# CoolderPSU.net
KiCad netlist of a schematic drawn in EAGLE
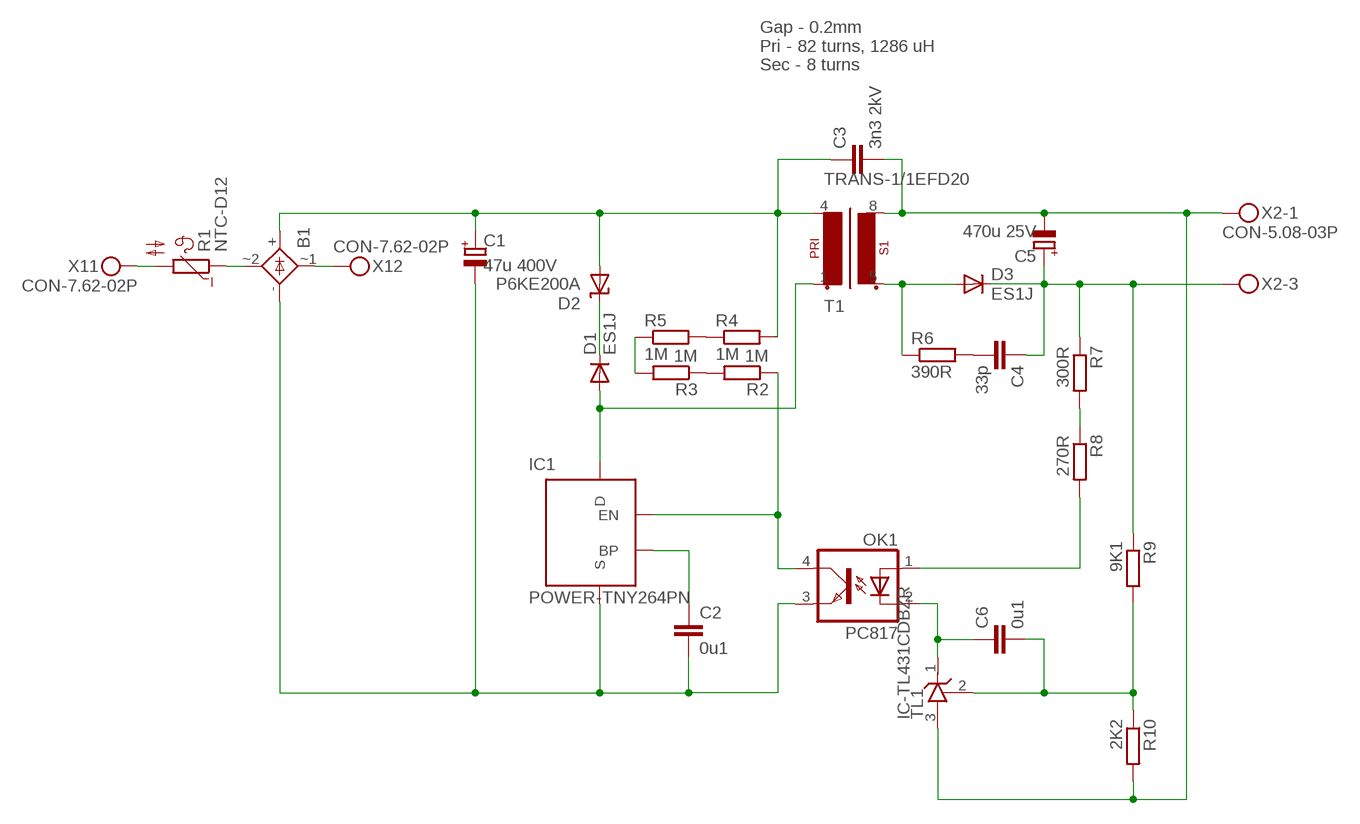
[diagram p0: schematic, sheet 1]

(export (version "E")
  (design (tool "Eeschema 10.0.6"))
  (components
    (comp (ref "B1")
      (value "RECTIFIERSOIC-8")
      (footprint "eagle-import:SOIC-4")
      (libsource (lib "eagle-import") (part "RECTIFIERSOIC-8"))
    )
    (comp (ref "C1")
      (value "47u 400V")
      (footprint "eagle-import:E7,5-16-32-HORIZ")
      (libsource (lib "eagle-import") (part "CAP-POL_E7,5-16"))
    )
    (comp (ref "C2")
      (value "0u1")
      (footprint "eagle-import:C0805")
      (libsource (lib "eagle-import") (part "CAP_0805"))
    )
    (comp (ref "C3")
      (value "3n3 2kV")
      (footprint "eagle-import:C050-024X044")
      (libsource (lib "eagle-import") (part "CAP_C50-024X044"))
    )
    (comp (ref "C4")
      (value "33p")
      (footprint "eagle-import:C0805")
      (libsource (lib "eagle-import") (part "CAP_0805"))
    )
    (comp (ref "C5")
      (value "470u 25V")
      (footprint "eagle-import:E2,5-7")
      (libsource (lib "eagle-import") (part "CAP-POL_E2.5-7"))
    )
    (comp (ref "C6")
      (value "0u1")
      (footprint "eagle-import:C0805")
      (libsource (lib "eagle-import") (part "CAP_0805"))
    )
    (comp (ref "D1")
      (value "ES1J")
      (footprint "eagle-import:DO214AC")
      (libsource (lib "eagle-import") (part "DIODE_ES1J"))
    )
    (comp (ref "D2")
      (value "P6KE200A")
      (footprint "eagle-import:DO15-12")
      (libsource (lib "eagle-import") (part "SUPRESSORDO-204AC"))
    )
    (comp (ref "D3")
      (value "ES1J")
      (footprint "eagle-import:DO214AC")
      (libsource (lib "eagle-import") (part "DIODE_ES1J"))
    )
    (comp (ref "IC1")
      (value "POWER-TNY264PN")
      (footprint "eagle-import:DIP-8B")
      (libsource (lib "eagle-import") (part "POWER-TNY264PN"))
    )
    (comp (ref "OK1")
      (value "PC817")
      (footprint "eagle-import:DIL04")
      (fields (field (name "MPN") "PC817X4J000F"))
      (libsource (lib "eagle-import") (part "OPTOTRANSPC817"))
    )
    (comp (ref "R1")
      (value "NTC-D12")
      (footprint "eagle-import:NTC-D12")
      (libsource (lib "eagle-import") (part "NTC-D12"))
    )
    (comp (ref "R2")
      (value "1M")
      (footprint "eagle-import:R1206")
      (libsource (lib "eagle-import") (part "R_1206"))
    )
    (comp (ref "R3")
      (value "1M")
      (footprint "eagle-import:R1206")
      (libsource (lib "eagle-import") (part "R_1206"))
    )
    (comp (ref "R4")
      (value "1M")
      (footprint "eagle-import:R1206")
      (libsource (lib "eagle-import") (part "R_1206"))
    )
    (comp (ref "R5")
      (value "1M")
      (footprint "eagle-import:R1206")
      (libsource (lib "eagle-import") (part "R_1206"))
    )
    (comp (ref "R6")
      (value "390R")
      (footprint "eagle-import:R1206")
      (libsource (lib "eagle-import") (part "R_1206"))
    )
    (comp (ref "R7")
      (value "300R")
      (footprint "eagle-import:R1206")
      (libsource (lib "eagle-import") (part "R_1206"))
    )
    (comp (ref "R8")
      (value "270R")
      (footprint "eagle-import:R1206")
      (libsource (lib "eagle-import") (part "R_1206"))
    )
    (comp (ref "R9")
      (value "9K1")
      (footprint "eagle-import:R1206")
      (libsource (lib "eagle-import") (part "R_1206"))
    )
    (comp (ref "R10")
      (value "2K2")
      (footprint "eagle-import:R1206")
      (libsource (lib "eagle-import") (part "R_1206"))
    )
    (comp (ref "T1")
      (value "TRANS-1/1EFD20")
      (footprint "eagle-import:EFD20_8PIN")
      (libsource (lib "eagle-import") (part "TRANS-1/1EFD20"))
    )
    (comp (ref "TL1")
      (value "IC-TL431CDBZR")
      (footprint "eagle-import:SOT23")
      (libsource (lib "eagle-import") (part "IC-TL431CDBZR"))
    )
    (comp (ref "X1")
      (value "CON-7.62-02P")
      (footprint "eagle-import:KF25C-7.62-02P-13")
      (libsource (lib "eagle-import") (part "CON-7.62-02P"))
    )
    (comp (ref "X2")
      (value "CON-5.08-03P")
      (footprint "eagle-import:MKDSN1,5_3-5,08")
      (libsource (lib "eagle-import") (part "CON-5.08-03P"))
    )
  )
  (nets
    (net (code "1") (name "Net-(B1-AC1)") (class "Default")
      (node (ref "B1") (pin "~1") (pinfunction "AC1_~1") (pintype "passive"))
      (node (ref "X1") (pin "P$2") (pinfunction "KL_P$2") (pintype "passive"))
    )
    (net (code "2") (name "Net-(B1-AC2)") (class "Default")
      (node (ref "B1") (pin "~2") (pinfunction "AC2_~2") (pintype "passive"))
      (node (ref "R1") (pin "1") (pinfunction "1_1") (pintype "passive"))
    )
    (net (code "3") (name "Net-(C4-Pad2)") (class "Default")
      (node (ref "C4") (pin "2") (pinfunction "2_2") (pintype "passive"))
      (node (ref "R6") (pin "2") (pinfunction "2_2") (pintype "passive"))
    )
    (net (code "4") (name "Net-(D1-PadC)") (class "Default")
      (node (ref "D1") (pin "C") (pinfunction "C_C") (pintype "passive"))
      (node (ref "D2") (pin "C") (pinfunction "C_C") (pintype "passive"))
    )
    (net (code "5") (name "Net-(IC1-BP)") (class "Default")
      (node (ref "C2") (pin "1") (pinfunction "1_1") (pintype "passive"))
      (node (ref "IC1") (pin "1") (pinfunction "BP_1") (pintype "input"))
    )
    (net (code "6") (name "Net-(IC1-D)") (class "Default")
      (node (ref "D1") (pin "A") (pinfunction "A_A") (pintype "passive"))
      (node (ref "IC1") (pin "5") (pinfunction "D_5") (pintype "input"))
      (node (ref "T1") (pin "1") (pinfunction "P1-1_1") (pintype "passive"))
    )
    (net (code "7") (name "Net-(IC1-EN)") (class "Default")
      (node (ref "IC1") (pin "4") (pinfunction "EN_4") (pintype "input"))
      (node (ref "OK1") (pin "4") (pinfunction "COL_4") (pintype "passive"))
      (node (ref "R2") (pin "1") (pinfunction "1_1") (pintype "passive"))
    )
    (net (code "8") (name "Net-(OK1-A)") (class "Default")
      (node (ref "OK1") (pin "1") (pinfunction "A_1") (pintype "passive"))
      (node (ref "R8") (pin "2") (pinfunction "2_2") (pintype "passive"))
    )
    (net (code "9") (name "Net-(OK1-C)") (class "Default")
      (node (ref "C6") (pin "1") (pinfunction "1_1") (pintype "passive"))
      (node (ref "OK1") (pin "2") (pinfunction "C_2") (pintype "passive"))
      (node (ref "TL1") (pin "1") (pinfunction "C_1") (pintype "passive"))
    )
    (net (code "10") (name "Net-(OK1-EMIT)") (class "Default")
      (node (ref "B1") (pin "-") (pinfunction "-_-") (pintype "passive"))
      (node (ref "C1") (pin "-") (pinfunction "-_-") (pintype "passive"))
      (node (ref "C2") (pin "2") (pinfunction "2_2") (pintype "passive"))
      (node (ref "IC1") (pin "2") (pinfunction "S_2") (pintype "input"))
      (node (ref "IC1") (pin "3") (pinfunction "S_3") (pintype "input"))
      (node (ref "IC1") (pin "7") (pinfunction "S_7") (pintype "input"))
      (node (ref "IC1") (pin "8") (pinfunction "S_8") (pintype "input"))
      (node (ref "OK1") (pin "3") (pinfunction "EMIT_3") (pintype "passive"))
    )
    (net (code "11") (name "Net-(R2-Pad2)") (class "Default")
      (node (ref "R2") (pin "2") (pinfunction "2_2") (pintype "passive"))
      (node (ref "R3") (pin "1") (pinfunction "1_1") (pintype "passive"))
    )
    (net (code "12") (name "Net-(R3-Pad2)") (class "Default")
      (node (ref "R3") (pin "2") (pinfunction "2_2") (pintype "passive"))
      (node (ref "R5") (pin "1") (pinfunction "1_1") (pintype "passive"))
    )
    (net (code "13") (name "Net-(R4-Pad1)") (class "Default")
      (node (ref "R4") (pin "1") (pinfunction "1_1") (pintype "passive"))
      (node (ref "R5") (pin "2") (pinfunction "2_2") (pintype "passive"))
    )
    (net (code "14") (name "Net-(R7-Pad2)") (class "Default")
      (node (ref "R7") (pin "2") (pinfunction "2_2") (pintype "passive"))
      (node (ref "R8") (pin "1") (pinfunction "1_1") (pintype "passive"))
    )
    (net (code "15") (name "Net-(T1-P1-2)") (class "Default")
      (node (ref "B1") (pin "+") (pinfunction "+_+") (pintype "passive"))
      (node (ref "C1") (pin "+") (pinfunction "+_+") (pintype "passive"))
      (node (ref "C3") (pin "1") (pinfunction "1_1") (pintype "passive"))
      (node (ref "D2") (pin "A") (pinfunction "A_A") (pintype "passive"))
      (node (ref "R4") (pin "2") (pinfunction "2_2") (pintype "passive"))
      (node (ref "T1") (pin "4") (pinfunction "P1-2_4") (pintype "passive"))
    )
    (net (code "16") (name "Net-(T1-S1-1)") (class "Default")
      (node (ref "D3") (pin "A") (pinfunction "A_A") (pintype "passive"))
      (node (ref "R6") (pin "1") (pinfunction "1_1") (pintype "passive"))
      (node (ref "T1") (pin "5") (pinfunction "S1-1_5") (pintype "passive"))
    )
    (net (code "17") (name "Net-(T1-S1-2)") (class "Default")
      (node (ref "C3") (pin "2") (pinfunction "2_2") (pintype "passive"))
      (node (ref "C5") (pin "-") (pinfunction "-_-") (pintype "passive"))
      (node (ref "R10") (pin "2") (pinfunction "2_2") (pintype "passive"))
      (node (ref "T1") (pin "8") (pinfunction "S1-2_8") (pintype "passive"))
      (node (ref "TL1") (pin "3") (pinfunction "A_3") (pintype "passive"))
      (node (ref "X2") (pin "1") (pinfunction "KL_1") (pintype "passive"))
    )
    (net (code "18") (name "Net-(TL1-R)") (class "Default")
      (node (ref "C6") (pin "2") (pinfunction "2_2") (pintype "passive"))
      (node (ref "R10") (pin "1") (pinfunction "1_1") (pintype "passive"))
      (node (ref "R9") (pin "2") (pinfunction "2_2") (pintype "passive"))
      (node (ref "TL1") (pin "2") (pinfunction "R_2") (pintype "passive"))
    )
    (net (code "19") (name "Net-(X1A-KL)") (class "Default")
      (node (ref "R1") (pin "2") (pinfunction "2_2") (pintype "passive"))
      (node (ref "X1") (pin "P$1") (pinfunction "KL_P$1") (pintype "passive"))
    )
    (net (code "20") (name "Net-(X2C-KL)") (class "Default")
      (node (ref "C4") (pin "1") (pinfunction "1_1") (pintype "passive"))
      (node (ref "C5") (pin "+") (pinfunction "+_+") (pintype "passive"))
      (node (ref "D3") (pin "C") (pinfunction "C_C") (pintype "passive"))
      (node (ref "R7") (pin "1") (pinfunction "1_1") (pintype "passive"))
      (node (ref "R9") (pin "1") (pinfunction "1_1") (pintype "passive"))
      (node (ref "X2") (pin "3") (pinfunction "KL_3") (pintype "passive"))
    )
  )
)
